# kriner-pc.net
KiCad netlist of a schematic drawn in EAGLE
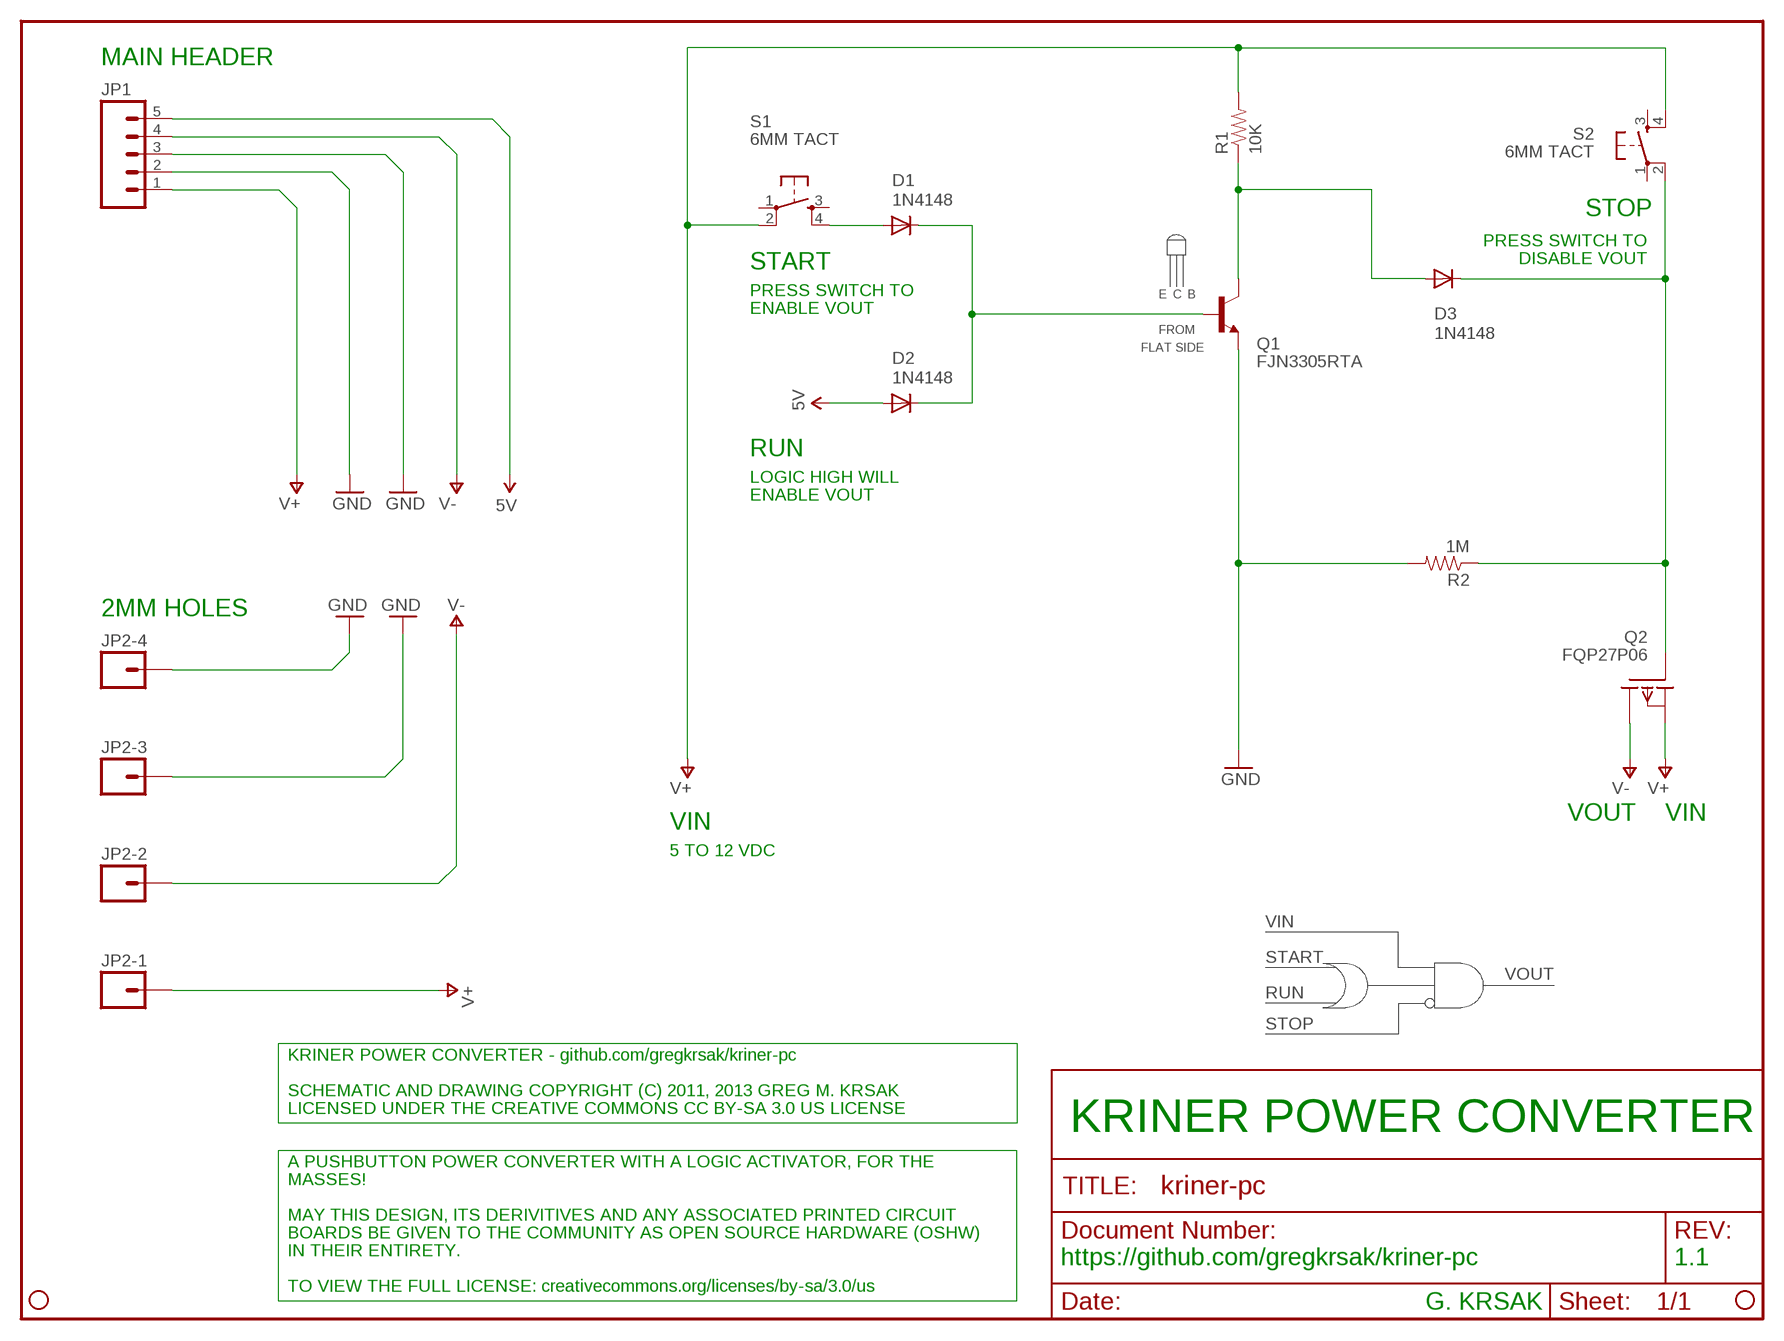
[diagram p0: schematic, sheet 1]

(export (version "E")
  (design (tool "Eeschema 10.0.6"))
  (components
    (comp (ref "D1")
      (value "1N4148")
      (footprint "eagle-import:DIODE-1N4148")
      (libsource (lib "eagle-import") (part "DIODE1N4148"))
    )
    (comp (ref "D2")
      (value "1N4148")
      (footprint "eagle-import:DIODE-1N4148")
      (libsource (lib "eagle-import") (part "DIODE1N4148"))
    )
    (comp (ref "D3")
      (value "1N4148")
      (footprint "eagle-import:DIODE-1N4148")
      (libsource (lib "eagle-import") (part "DIODE1N4148"))
    )
    (comp (ref "JP1")
      (value "M05LOCK")
      (footprint "eagle-import:1X05_LOCK")
      (libsource (lib "eagle-import") (part "M05LOCK"))
    )
    (comp (ref "JP2")
      (value "STAND-OFF")
      (footprint "eagle-import:STAND-OFF")
      (libsource (lib "eagle-import") (part "STAND-OFF"))
    )
    (comp (ref "JP2-1")
      (value "M01PTH_2MM")
      (footprint "eagle-import:1X01_2MM")
      (libsource (lib "eagle-import") (part "M01PTH_2MM"))
    )
    (comp (ref "JP2-2")
      (value "M01PTH_2MM")
      (footprint "eagle-import:1X01_2MM")
      (libsource (lib "eagle-import") (part "M01PTH_2MM"))
    )
    (comp (ref "JP2-3")
      (value "M01PTH_2MM")
      (footprint "eagle-import:1X01_2MM")
      (libsource (lib "eagle-import") (part "M01PTH_2MM"))
    )
    (comp (ref "JP2-4")
      (value "M01PTH_2MM")
      (footprint "eagle-import:1X01_2MM")
      (libsource (lib "eagle-import") (part "M01PTH_2MM"))
    )
    (comp (ref "JP3")
      (value "STAND-OFF")
      (footprint "eagle-import:STAND-OFF")
      (libsource (lib "eagle-import") (part "STAND-OFF"))
    )
    (comp (ref "Q1")
      (value "FJN3305RTA")
      (footprint "eagle-import:TO92-ECB")
      (libsource (lib "eagle-import") (part "-NPN-TO92-ECB"))
    )
    (comp (ref "Q2")
      (value "FQP27P06")
      (footprint "eagle-import:TO220")
      (libsource (lib "eagle-import") (part "SUP65P06-20"))
    )
    (comp (ref "R1")
      (value "10K")
      (footprint "eagle-import:AXIAL-0.3")
      (libsource (lib "eagle-import") (part "RESISTORAXIAL-0.3"))
    )
    (comp (ref "R2")
      (value "1M")
      (footprint "eagle-import:AXIAL-0.3")
      (libsource (lib "eagle-import") (part "RESISTORAXIAL-0.3"))
    )
    (comp (ref "S1")
      (value "6MM TACT")
      (footprint "eagle-import:TACTILE-PTH")
      (libsource (lib "eagle-import") (part "TAC_SWITCHPTH"))
    )
    (comp (ref "S2")
      (value "6MM TACT")
      (footprint "eagle-import:TACTILE-PTH")
      (libsource (lib "eagle-import") (part "TAC_SWITCHPTH"))
    )
  )
  (nets
    (net (code "1") (name "5V") (class "Default")
      (node (ref "D2") (pin "A") (pinfunction "A_A") (pintype "passive"))
      (node (ref "JP1") (pin "5") (pinfunction "5_5") (pintype "passive"))
    )
    (net (code "2") (name "GND") (class "Default")
      (node (ref "JP1") (pin "2") (pinfunction "2_2") (pintype "passive"))
      (node (ref "JP1") (pin "3") (pinfunction "3_3") (pintype "passive"))
      (node (ref "JP2-3") (pin "1") (pinfunction "1_1") (pintype "passive"))
      (node (ref "JP2-4") (pin "1") (pinfunction "1_1") (pintype "passive"))
      (node (ref "Q1") (pin "E") (pinfunction "E_E") (pintype "passive"))
      (node (ref "R2") (pin "P$2") (pinfunction "2_P$2") (pintype "passive"))
    )
    (net (code "3") (name "Net-(D1-PadA)") (class "Default")
      (node (ref "D1") (pin "A") (pinfunction "A_A") (pintype "passive"))
      (node (ref "S1") (pin "4") (pinfunction "4_4") (pintype "passive"))
    )
    (net (code "4") (name "Net-(D1-PadC)") (class "Default")
      (node (ref "D1") (pin "C") (pinfunction "C_C") (pintype "passive"))
      (node (ref "D2") (pin "C") (pinfunction "C_C") (pintype "passive"))
      (node (ref "Q1") (pin "B") (pinfunction "B_B") (pintype "passive"))
    )
    (net (code "5") (name "Net-(Q2-G)") (class "Default")
      (node (ref "D3") (pin "C") (pinfunction "C_C") (pintype "passive"))
      (node (ref "Q2") (pin "1") (pinfunction "G_1") (pintype "passive"))
      (node (ref "R2") (pin "P$1") (pinfunction "1_P$1") (pintype "passive"))
      (node (ref "S2") (pin "2") (pinfunction "2_2") (pintype "passive"))
    )
    (net (code "6") (name "Net-(R1-1)") (class "Default")
      (node (ref "D3") (pin "A") (pinfunction "A_A") (pintype "passive"))
      (node (ref "Q1") (pin "C") (pinfunction "C_C") (pintype "passive"))
      (node (ref "R1") (pin "P$1") (pinfunction "1_P$1") (pintype "passive"))
    )
    (net (code "7") (name "V+") (class "Default")
      (node (ref "JP1") (pin "1") (pinfunction "1_1") (pintype "passive"))
      (node (ref "JP2-1") (pin "1") (pinfunction "1_1") (pintype "passive"))
      (node (ref "Q2") (pin "3") (pinfunction "S_3") (pintype "passive"))
      (node (ref "R1") (pin "P$2") (pinfunction "2_P$2") (pintype "passive"))
      (node (ref "S1") (pin "2") (pinfunction "2_2") (pintype "passive"))
      (node (ref "S2") (pin "4") (pinfunction "4_4") (pintype "passive"))
    )
    (net (code "8") (name "V-") (class "Default")
      (node (ref "JP1") (pin "4") (pinfunction "4_4") (pintype "passive"))
      (node (ref "JP2-2") (pin "1") (pinfunction "1_1") (pintype "passive"))
      (node (ref "Q2") (pin "2") (pinfunction "D_2") (pintype "passive"))
    )
    (net (code "9") (name "unconnected-(S1-Pad1)") (class "Default")
      (node (ref "S1") (pin "1") (pinfunction "1_1") (pintype "passive"))
    )
    (net (code "10") (name "unconnected-(S1-Pad3)") (class "Default")
      (node (ref "S1") (pin "3") (pinfunction "3_3") (pintype "passive"))
    )
    (net (code "11") (name "unconnected-(S2-Pad1)") (class "Default")
      (node (ref "S2") (pin "1") (pinfunction "1_1") (pintype "passive"))
    )
    (net (code "12") (name "unconnected-(S2-Pad3)") (class "Default")
      (node (ref "S2") (pin "3") (pinfunction "3_3") (pintype "passive"))
    )
  )
)
